# Actuator.net
KiCad netlist of a schematic drawn in Altium Designer
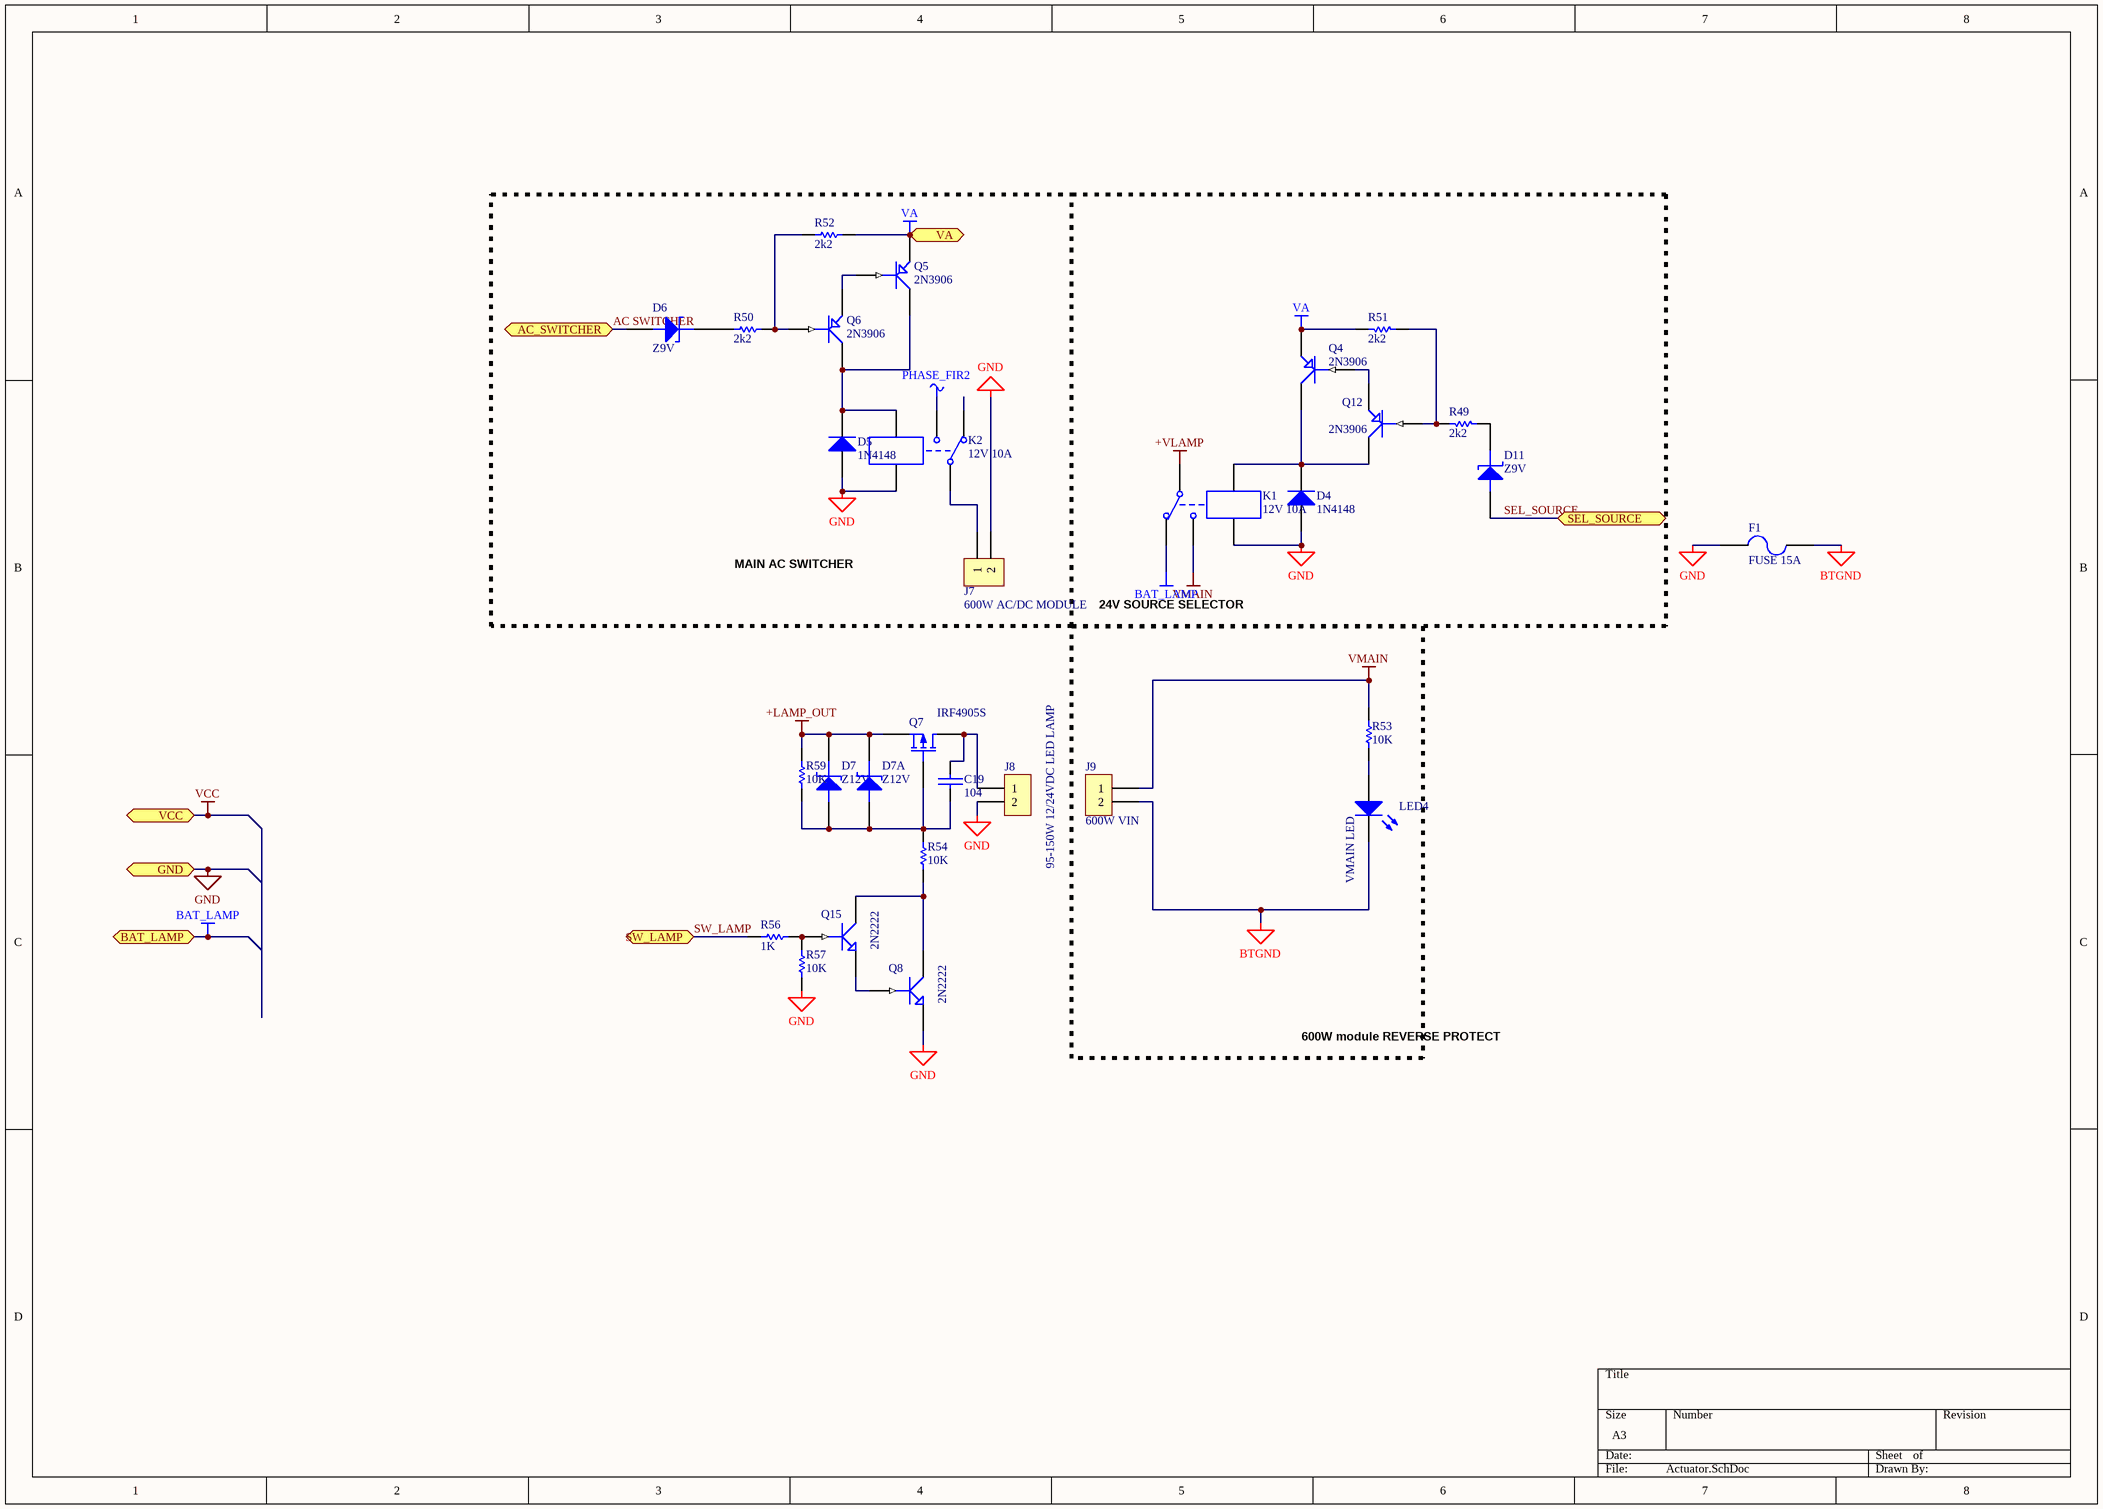
[diagram p0: Actuator.SchDoc]

(export (version "E")
  (design (tool "Eeschema 10.0.6"))
  (components
    (comp (ref "C19")
      (value "104")
      (footprint "C6-0805_N")
      (description "Capacitor")
      (libsource (lib "*") (part "CAP"))
    )
    (comp (ref "D4")
      (value "1N4148")
      (footprint "SOD80, LL-34")
      (description "1 Amp General Purpose Rectifier")
      (fields (field (name "PUBLISHER") "Altium Limited"))
      (libsource (lib "*") (part "Diode 1N4007"))
    )
    (comp (ref "D5")
      (value "1N4148")
      (footprint "SOD80, LL-34")
      (description "1 Amp General Purpose Rectifier")
      (fields (field (name "PUBLISHER") "Altium Limited"))
      (libsource (lib "*") (part "Diode 1N4007"))
    )
    (comp (ref "D6")
      (value "Z9V")
      (footprint "SOD80, LL-34")
      (description "Zener Diode")
      (libsource (lib "*") (part "ZENER2"))
    )
    (comp (ref "D7")
      (value "Z12V")
      (footprint "DO-35")
      (description "Zener Diode")
      (libsource (lib "*") (part "ZENER2"))
    )
    (comp (ref "D7A")
      (value "Z12V")
      (footprint "SOD80, LL-34")
      (description "Zener Diode")
      (libsource (lib "*") (part "ZENER2"))
    )
    (comp (ref "D11")
      (value "Z9V")
      (footprint "SOD80, LL-34")
      (description "Zener Diode")
      (libsource (lib "*") (part "ZENER2"))
    )
    (comp (ref "F1")
      (value "FUSE 15A")
      (footprint "FUSE2")
      (description "Fuse")
      (libsource (lib "*") (part "FUSE2"))
    )
    (comp (ref "J7")
      (value "600W AC/DC MODULE")
      (footprint "TERMINAL2")
      (description "Connector")
      (libsource (lib "*") (part "CON2"))
    )
    (comp (ref "J8")
      (value "95-150W 12/24VDC LED LAMP")
      (footprint "TERMINAL2")
      (description "Connector")
      (libsource (lib "") (part "CON2_2"))
    )
    (comp (ref "J9")
      (value "600W VIN")
      (footprint "TERMINAL2")
      (description "Connector")
      (libsource (lib "") (part "CON2_1"))
    )
    (comp (ref "K1")
      (value "12V 10A")
      (footprint "RELAYVUONG")
      (description "G5LA-10A/250VAC / SRC-12VDC-SL-C")
      (fields (field (name "PUBLISHER") "Altium Limited"))
      (libsource (lib "Miscellaneous Devices") (part "Relay-SPDT"))
    )
    (comp (ref "K2")
      (value "12V 10A")
      (footprint "RELAYVUONG")
      (description "G5LA-10A/250VAC / SRC-12VDC-SL-C")
      (fields (field (name "PUBLISHER") "Altium Limited"))
      (libsource (lib "Miscellaneous Devices") (part "Relay-SPDT"))
    )
    (comp (ref "LED4")
      (value "VMAIN LED")
      (footprint "led3mm")
      (description "Typical BLUE SiC LED")
      (fields (field (name "PUBLISHER") "Altium Limited"))
      (libsource (lib "Miscellaneous Devices") (part "LED3"))
    )
    (comp (ref "Q4")
      (value "2N3906")
      (footprint "SOT23-3")
      (description "PNP Transistor")
      (libsource (lib "*") (part "PNP1"))
    )
    (comp (ref "Q5")
      (value "2N3906")
      (footprint "SOT23-3")
      (description "PNP Transistor")
      (libsource (lib "*") (part "PNP1"))
    )
    (comp (ref "Q6")
      (value "2N3906")
      (footprint "SOT23-3")
      (description "PNP Transistor")
      (libsource (lib "*") (part "PNP1"))
    )
    (comp (ref "Q7")
      (value "IRF4905S")
      (footprint "D2PAK-3")
      (description "HEXFET Power P MOSFET")
      (fields (field (name "PUBLISHER") "Altium Limited"))
      (libsource (lib "Miscellaneous Devices") (part "MOSFET-P"))
    )
    (comp (ref "Q8")
      (value "2N2222")
      (footprint "SOT23-3")
      (description "NPN Transistor")
      (libsource (lib "*") (part "NPN1"))
    )
    (comp (ref "Q12")
      (value "2N3906")
      (footprint "SOT23-3")
      (description "PNP Transistor")
      (libsource (lib "*") (part "PNP1"))
    )
    (comp (ref "Q15")
      (value "2N2222")
      (footprint "SOT23-3")
      (description "NPN Transistor")
      (libsource (lib "*") (part "NPN1"))
    )
    (comp (ref "R49")
      (value "2k2")
      (footprint "6-0805_N")
      (description "Semiconductor Resistor")
      (fields (field (name "PUBLISHER") "Altium Limited"))
      (libsource (lib "*") (part "Res Semi"))
    )
    (comp (ref "R50")
      (value "2k2")
      (footprint "6-0805_N")
      (description "Semiconductor Resistor")
      (fields (field (name "PUBLISHER") "Altium Limited"))
      (libsource (lib "*") (part "Res Semi"))
    )
    (comp (ref "R51")
      (value "2k2")
      (footprint "6-0805_N")
      (description "Semiconductor Resistor")
      (fields (field (name "PUBLISHER") "Altium Limited"))
      (libsource (lib "*") (part "Res Semi"))
    )
    (comp (ref "R52")
      (value "2k2")
      (footprint "6-0805_N")
      (description "Semiconductor Resistor")
      (fields (field (name "PUBLISHER") "Altium Limited"))
      (libsource (lib "*") (part "Res Semi"))
    )
    (comp (ref "R53")
      (value "10K")
      (footprint "6-0805_N")
      (description "Semiconductor Resistor")
      (fields (field (name "PUBLISHER") "*"))
      (libsource (lib "*") (part "Res Semi"))
    )
    (comp (ref "R54")
      (value "10K")
      (footprint "6-0805_N")
      (description "Semiconductor Resistor")
      (fields (field (name "PUBLISHER") "Altium Limited"))
      (libsource (lib "*") (part "Res Semi"))
    )
    (comp (ref "R56")
      (value "1K")
      (footprint "6-0805_N")
      (description "Semiconductor Resistor")
      (fields (field (name "PUBLISHER") "Altium Limited"))
      (libsource (lib "*") (part "Res Semi"))
    )
    (comp (ref "R57")
      (value "10K")
      (footprint "6-0805_N")
      (description "Semiconductor Resistor")
      (fields (field (name "PUBLISHER") "Altium Limited"))
      (libsource (lib "*") (part "Res Semi"))
    )
    (comp (ref "R59")
      (value "10K")
      (footprint "6-0805_N")
      (description "Semiconductor Resistor")
      (fields (field (name "PUBLISHER") "Altium Limited"))
      (libsource (lib "*") (part "Res Semi"))
    )
  )
  (nets
    (net (code "1") (name "+LAMP_OUT") (class "Default")
      (node (ref "D7") (pin "2") (pinfunction "K_2") (pintype "passive"))
      (node (ref "D7A") (pin "2") (pinfunction "K_2") (pintype "passive"))
      (node (ref "Q7") (pin "3") (pinfunction "S_3") (pintype "passive"))
      (node (ref "R59") (pin "2") (pinfunction "2_2") (pintype "passive"))
    )
    (net (code "2") (name "+VLAMP") (class "Default")
      (node (ref "K1") (pin "1") (pinfunction "1_1") (pintype "passive"))
    )
    (net (code "3") (name "/AC SWITCHER") (class "Default")
      (node (ref "D6") (pin "1") (pinfunction "A_1") (pintype "passive"))
    )
    (net (code "4") (name "/SEL_SOURCE") (class "Default")
      (node (ref "D11") (pin "1") (pinfunction "A_1") (pintype "passive"))
    )
    (net (code "5") (name "/SW_LAMP") (class "Default")
      (node (ref "R56") (pin "1") (pinfunction "1_1") (pintype "passive"))
    )
    (net (code "6") (name "BAT_LAMP") (class "Default")
      (node (ref "K1") (pin "2") (pinfunction "2_2") (pintype "passive"))
    )
    (net (code "7") (name "BTGND") (class "Default")
      (node (ref "F1") (pin "2") (pinfunction "2_2") (pintype "passive"))
      (node (ref "J9") (pin "2") (pinfunction "2_2") (pintype "passive"))
      (node (ref "LED4") (pin "2") (pinfunction "K_2") (pintype "passive"))
    )
    (net (code "8") (name "GND") (class "Default")
      (node (ref "D4") (pin "1") (pinfunction "A_1") (pintype "passive"))
      (node (ref "D5") (pin "1") (pinfunction "A_1") (pintype "passive"))
      (node (ref "F1") (pin "1") (pinfunction "1_1") (pintype "passive"))
      (node (ref "J7") (pin "2") (pinfunction "2_2") (pintype "passive"))
      (node (ref "J8") (pin "2") (pinfunction "2_2") (pintype "passive"))
      (node (ref "K1") (pin "5") (pinfunction "5_5") (pintype "passive"))
      (node (ref "K2") (pin "4") (pinfunction "4_4") (pintype "passive"))
      (node (ref "Q8") (pin "2") (pinfunction "E_2") (pintype "passive"))
      (node (ref "R57") (pin "1") (pinfunction "1_1") (pintype "passive"))
    )
    (net (code "9") (name "Net-(D4-K)") (class "Default")
      (node (ref "D4") (pin "2") (pinfunction "K_2") (pintype "passive"))
      (node (ref "K1") (pin "4") (pinfunction "4_4") (pintype "passive"))
      (node (ref "Q12") (pin "3") (pinfunction "C_3") (pintype "passive"))
      (node (ref "Q4") (pin "3") (pinfunction "C_3") (pintype "passive"))
    )
    (net (code "10") (name "Net-(D5-K)") (class "Default")
      (node (ref "D5") (pin "2") (pinfunction "K_2") (pintype "passive"))
      (node (ref "K2") (pin "5") (pinfunction "5_5") (pintype "passive"))
      (node (ref "Q5") (pin "3") (pinfunction "C_3") (pintype "passive"))
      (node (ref "Q6") (pin "3") (pinfunction "C_3") (pintype "passive"))
    )
    (net (code "11") (name "Net-(D6-K)") (class "Default")
      (node (ref "D6") (pin "2") (pinfunction "K_2") (pintype "passive"))
      (node (ref "R50") (pin "1") (pinfunction "1_1") (pintype "passive"))
    )
    (net (code "12") (name "Net-(D7-A)") (class "Default")
      (node (ref "C19") (pin "2") (pinfunction "2_2") (pintype "passive"))
      (node (ref "D7") (pin "1") (pinfunction "A_1") (pintype "passive"))
      (node (ref "D7A") (pin "1") (pinfunction "A_1") (pintype "passive"))
      (node (ref "Q7") (pin "1") (pinfunction "G_1") (pintype "passive"))
      (node (ref "R54") (pin "2") (pinfunction "2_2") (pintype "passive"))
      (node (ref "R59") (pin "1") (pinfunction "1_1") (pintype "passive"))
    )
    (net (code "13") (name "Net-(D11-K)") (class "Default")
      (node (ref "D11") (pin "2") (pinfunction "K_2") (pintype "passive"))
      (node (ref "R49") (pin "1") (pinfunction "1_1") (pintype "passive"))
    )
    (net (code "14") (name "Net-(J7-Pad1)") (class "Default")
      (node (ref "J7") (pin "1") (pinfunction "1_1") (pintype "passive"))
      (node (ref "K2") (pin "1") (pinfunction "1_1") (pintype "passive"))
    )
    (net (code "15") (name "Net-(LED4-A)") (class "Default")
      (node (ref "LED4") (pin "1") (pinfunction "A_1") (pintype "passive"))
      (node (ref "R53") (pin "1") (pinfunction "1_1") (pintype "passive"))
    )
    (net (code "16") (name "Net-(Q5-B)") (class "Default")
      (node (ref "Q5") (pin "1") (pinfunction "B_1") (pintype "input"))
      (node (ref "Q6") (pin "2") (pinfunction "E_2") (pintype "passive"))
    )
    (net (code "17") (name "Net-(Q6-B)") (class "Default")
      (node (ref "Q6") (pin "1") (pinfunction "B_1") (pintype "input"))
      (node (ref "R50") (pin "2") (pinfunction "2_2") (pintype "passive"))
      (node (ref "R52") (pin "1") (pinfunction "1_1") (pintype "passive"))
    )
    (net (code "18") (name "Net-(Q7-D)") (class "Default")
      (node (ref "C19") (pin "1") (pinfunction "1_1") (pintype "passive"))
      (node (ref "J8") (pin "1") (pinfunction "1_1") (pintype "passive"))
      (node (ref "Q7") (pin "2") (pinfunction "D_2") (pintype "passive"))
    )
    (net (code "19") (name "Net-(Q12-B)") (class "Default")
      (node (ref "Q12") (pin "1") (pinfunction "B_1") (pintype "input"))
      (node (ref "R49") (pin "2") (pinfunction "2_2") (pintype "passive"))
      (node (ref "R51") (pin "1") (pinfunction "1_1") (pintype "passive"))
    )
    (net (code "20") (name "Net-(Q12-E)") (class "Default")
      (node (ref "Q12") (pin "2") (pinfunction "E_2") (pintype "passive"))
      (node (ref "Q4") (pin "1") (pinfunction "B_1") (pintype "input"))
    )
    (net (code "21") (name "Net-(Q15-B)") (class "Default")
      (node (ref "Q15") (pin "1") (pinfunction "B_1") (pintype "input"))
      (node (ref "R56") (pin "2") (pinfunction "2_2") (pintype "passive"))
      (node (ref "R57") (pin "2") (pinfunction "2_2") (pintype "passive"))
    )
    (net (code "22") (name "Net-(Q15-C)") (class "Default")
      (node (ref "Q15") (pin "3") (pinfunction "C_3") (pintype "passive"))
      (node (ref "Q8") (pin "3") (pinfunction "C_3") (pintype "passive"))
      (node (ref "R54") (pin "1") (pinfunction "1_1") (pintype "passive"))
    )
    (net (code "23") (name "Net-(Q15-E)") (class "Default")
      (node (ref "Q15") (pin "2") (pinfunction "E_2") (pintype "passive"))
      (node (ref "Q8") (pin "1") (pinfunction "B_1") (pintype "input"))
    )
    (net (code "24") (name "PHASE_FIR2") (class "Default")
      (node (ref "K2") (pin "3") (pinfunction "3_3") (pintype "passive"))
    )
    (net (code "25") (name "VA") (class "Default")
      (node (ref "Q4") (pin "2") (pinfunction "E_2") (pintype "passive"))
      (node (ref "Q5") (pin "2") (pinfunction "E_2") (pintype "passive"))
      (node (ref "R51") (pin "2") (pinfunction "2_2") (pintype "passive"))
      (node (ref "R52") (pin "2") (pinfunction "2_2") (pintype "passive"))
    )
    (net (code "27") (name "VMAIN") (class "Default")
      (node (ref "J9") (pin "1") (pinfunction "1_1") (pintype "passive"))
      (node (ref "K1") (pin "3") (pinfunction "3_3") (pintype "passive"))
      (node (ref "R53") (pin "2") (pinfunction "2_2") (pintype "passive"))
    )
    (net (code "28") (name "unconnected-(K2-Pad2)") (class "Default")
      (node (ref "K2") (pin "2") (pinfunction "2_2") (pintype "passive"))
    )
  )
)
